# SingleResistor.net
KiCad netlist of a schematic drawn in EAGLE
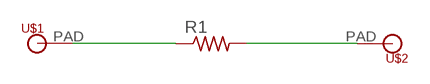
[diagram p0: schematic, sheet 1]

(export (version "E")
  (design (tool "Eeschema 10.0.6"))
  (components
    (comp (ref "R1")
      (value "R-US_VMTB60")
      (footprint "eagle-import:VMTB60")
      (libsource (lib "eagle-import") (part "R-US_VMTB60"))
    )
    (comp (ref "U$1")
      (value "MICROBIT_PAD")
      (footprint "eagle-import:MICROBIT_PAD")
      (libsource (lib "eagle-import") (part "MICROBIT_PAD"))
    )
    (comp (ref "U$2")
      (value "MICROBIT_PAD")
      (footprint "eagle-import:MICROBIT_PAD")
      (libsource (lib "eagle-import") (part "MICROBIT_PAD"))
    )
  )
  (nets
    (net (code "1") (name "Net-(U$1-P$1)") (class "Default")
      (node (ref "R1") (pin "1") (pinfunction "1_1") (pintype "passive"))
      (node (ref "U$1") (pin "PAD") (pinfunction "P$1_PAD") (pintype "bidirectional"))
    )
    (net (code "2") (name "Net-(U$2-P$1)") (class "Default")
      (node (ref "R1") (pin "2") (pinfunction "2_2") (pintype "passive"))
      (node (ref "U$2") (pin "PAD") (pinfunction "P$1_PAD") (pintype "bidirectional"))
    )
  )
)
